# zero_board.net
KiCad netlist of a schematic drawn in EAGLE
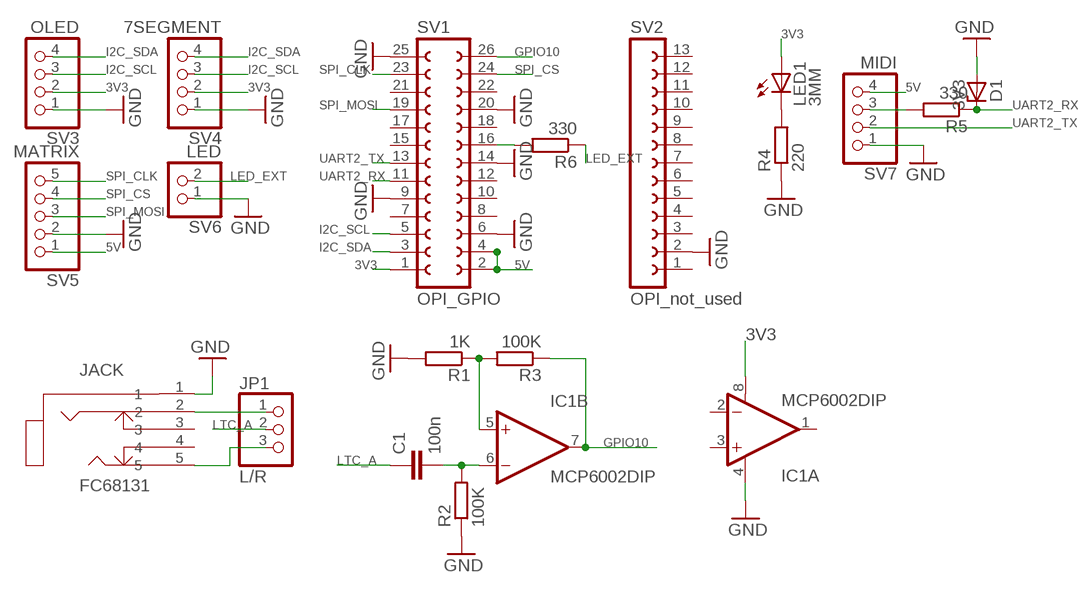
[diagram p0: schematic, sheet 1]

(export (version "E")
  (design (tool "Eeschema 10.0.6"))
  (components
    (comp (ref "C1")
      (value "100n")
      (footprint "eagle-import:C050-024X044")
      (libsource (lib "eagle-import") (part "C-EU050-024X044"))
    )
    (comp (ref "D1")
      (value "3V3")
      (footprint "eagle-import:ZDIO-2.5")
      (libsource (lib "eagle-import") (part "ZENER-DIODEZD-2.5"))
    )
    (comp (ref "IC1")
      (value "MCP6002DIP")
      (footprint "eagle-import:DIP08")
      (libsource (lib "eagle-import") (part "MCP6002DIP"))
    )
    (comp (ref "JACK")
      (value "FC68131")
      (footprint "eagle-import:FC68131-5P")
      (libsource (lib "eagle-import") (part "FC68131"))
    )
    (comp (ref "JP1")
      (value "L/R")
      (footprint "eagle-import:1X03")
      (libsource (lib "eagle-import") (part "PINHD-1X3"))
    )
    (comp (ref "LED1")
      (value "3MM")
      (footprint "eagle-import:LED3MM")
      (libsource (lib "eagle-import") (part "LED3MM"))
    )
    (comp (ref "R1")
      (value "1K")
      (footprint "eagle-import:0204_5")
      (libsource (lib "eagle-import") (part "R-EU_0204/5"))
    )
    (comp (ref "R2")
      (value "100K")
      (footprint "eagle-import:0204_5")
      (libsource (lib "eagle-import") (part "R-EU_0204/5"))
    )
    (comp (ref "R3")
      (value "100K")
      (footprint "eagle-import:0204_5")
      (libsource (lib "eagle-import") (part "R-EU_0204/5"))
    )
    (comp (ref "R4")
      (value "220")
      (footprint "eagle-import:0204_5")
      (libsource (lib "eagle-import") (part "R-EU_0204/5"))
    )
    (comp (ref "R5")
      (value "330")
      (footprint "eagle-import:0204V")
      (libsource (lib "eagle-import") (part "R-EU_0204/2V"))
    )
    (comp (ref "R6")
      (value "330")
      (footprint "eagle-import:0204V")
      (libsource (lib "eagle-import") (part "R-EU_0204/2V"))
    )
    (comp (ref "SV1")
      (value "OPI_GPIO")
      (footprint "eagle-import:FE13-2")
      (libsource (lib "eagle-import") (part "FE13-2"))
    )
    (comp (ref "SV2")
      (value "OPI_not_used")
      (footprint "eagle-import:FE13")
      (libsource (lib "eagle-import") (part "FE13-1"))
    )
    (comp (ref "SV3")
      (value "OLED")
      (footprint "eagle-import:1X04")
      (libsource (lib "eagle-import") (part "PINHD-1X4"))
    )
    (comp (ref "SV4")
      (value "7SEGMENT")
      (footprint "eagle-import:1X04")
      (libsource (lib "eagle-import") (part "PINHD-1X4"))
    )
    (comp (ref "SV5")
      (value "MATRIX")
      (footprint "eagle-import:1X05")
      (libsource (lib "eagle-import") (part "PINHD-1X5"))
    )
    (comp (ref "SV6")
      (value "LED")
      (footprint "eagle-import:1X02")
      (libsource (lib "eagle-import") (part "PINHD-1X2"))
    )
    (comp (ref "SV7")
      (value "MIDI")
      (footprint "eagle-import:1X04")
      (libsource (lib "eagle-import") (part "PINHD-1X4"))
    )
  )
  (nets
    (net (code "1") (name "/3V3") (class "Default")
      (node (ref "IC1") (pin "8") (pinfunction "V+_8") (pintype "power_in"))
      (node (ref "LED1") (pin "A") (pinfunction "A_A") (pintype "passive"))
      (node (ref "SV1") (pin "1") (pinfunction "1_1") (pintype "passive"))
      (node (ref "SV3") (pin "2") (pinfunction "2_2") (pintype "passive"))
      (node (ref "SV4") (pin "2") (pinfunction "2_2") (pintype "passive"))
    )
    (net (code "2") (name "/5V") (class "Default")
      (node (ref "SV1") (pin "2") (pinfunction "2_2") (pintype "passive"))
      (node (ref "SV1") (pin "4") (pinfunction "4_4") (pintype "passive"))
      (node (ref "SV5") (pin "1") (pinfunction "1_1") (pintype "passive"))
      (node (ref "SV7") (pin "4") (pinfunction "4_4") (pintype "passive"))
    )
    (net (code "3") (name "/GPIO10") (class "Default")
      (node (ref "IC1") (pin "7") (pinfunction "OUT_7") (pintype "output"))
      (node (ref "R3") (pin "1") (pinfunction "1_1") (pintype "passive"))
      (node (ref "SV1") (pin "26") (pinfunction "26_26") (pintype "passive"))
    )
    (net (code "4") (name "/I2C_SCL") (class "Default")
      (node (ref "SV1") (pin "5") (pinfunction "5_5") (pintype "passive"))
      (node (ref "SV3") (pin "3") (pinfunction "3_3") (pintype "passive"))
      (node (ref "SV4") (pin "3") (pinfunction "3_3") (pintype "passive"))
    )
    (net (code "5") (name "/I2C_SDA") (class "Default")
      (node (ref "SV1") (pin "3") (pinfunction "3_3") (pintype "passive"))
      (node (ref "SV3") (pin "4") (pinfunction "4_4") (pintype "passive"))
      (node (ref "SV4") (pin "4") (pinfunction "4_4") (pintype "passive"))
    )
    (net (code "6") (name "/LED_EXT") (class "Default")
      (node (ref "R6") (pin "1") (pinfunction "1_1") (pintype "passive"))
      (node (ref "SV6") (pin "2") (pinfunction "2_2") (pintype "passive"))
    )
    (net (code "7") (name "/LTC_A") (class "Default")
      (node (ref "C1") (pin "1") (pinfunction "1_1") (pintype "passive"))
      (node (ref "JP1") (pin "2") (pinfunction "2_2") (pintype "passive"))
    )
    (net (code "8") (name "/SPI_CLK") (class "Default")
      (node (ref "SV1") (pin "23") (pinfunction "23_23") (pintype "passive"))
      (node (ref "SV5") (pin "5") (pinfunction "5_5") (pintype "passive"))
    )
    (net (code "9") (name "/SPI_CS") (class "Default")
      (node (ref "SV1") (pin "24") (pinfunction "24_24") (pintype "passive"))
      (node (ref "SV5") (pin "4") (pinfunction "4_4") (pintype "passive"))
    )
    (net (code "10") (name "/SPI_MOSI") (class "Default")
      (node (ref "SV1") (pin "19") (pinfunction "19_19") (pintype "passive"))
      (node (ref "SV5") (pin "3") (pinfunction "3_3") (pintype "passive"))
    )
    (net (code "11") (name "/UART2_RX") (class "Default")
      (node (ref "D1") (pin "C") (pinfunction "C_C") (pintype "passive"))
      (node (ref "R5") (pin "1") (pinfunction "1_1") (pintype "passive"))
      (node (ref "SV1") (pin "11") (pinfunction "11_11") (pintype "passive"))
    )
    (net (code "12") (name "/UART2_TX") (class "Default")
      (node (ref "SV1") (pin "13") (pinfunction "13_13") (pintype "passive"))
      (node (ref "SV7") (pin "2") (pinfunction "2_2") (pintype "passive"))
    )
    (net (code "13") (name "GND") (class "Default")
      (node (ref "D1") (pin "A") (pinfunction "A_A") (pintype "passive"))
      (node (ref "IC1") (pin "4") (pinfunction "V-_4") (pintype "power_in"))
      (node (ref "JACK") (pin "1") (pinfunction "1_1") (pintype "bidirectional"))
      (node (ref "R1") (pin "2") (pinfunction "2_2") (pintype "passive"))
      (node (ref "R2") (pin "1") (pinfunction "1_1") (pintype "passive"))
      (node (ref "R4") (pin "1") (pinfunction "1_1") (pintype "passive"))
      (node (ref "SV1") (pin "14") (pinfunction "14_14") (pintype "passive"))
      (node (ref "SV1") (pin "20") (pinfunction "20_20") (pintype "passive"))
      (node (ref "SV1") (pin "25") (pinfunction "25_25") (pintype "passive"))
      (node (ref "SV1") (pin "6") (pinfunction "6_6") (pintype "passive"))
      (node (ref "SV1") (pin "9") (pinfunction "9_9") (pintype "passive"))
      (node (ref "SV2") (pin "2") (pinfunction "2_2") (pintype "passive"))
      (node (ref "SV3") (pin "1") (pinfunction "1_1") (pintype "passive"))
      (node (ref "SV4") (pin "1") (pinfunction "1_1") (pintype "passive"))
      (node (ref "SV5") (pin "2") (pinfunction "2_2") (pintype "passive"))
      (node (ref "SV6") (pin "1") (pinfunction "1_1") (pintype "passive"))
      (node (ref "SV7") (pin "1") (pinfunction "1_1") (pintype "passive"))
    )
    (net (code "14") (name "Net-(IC1B-+IN)") (class "Default")
      (node (ref "IC1") (pin "5") (pinfunction "+IN_5") (pintype "input"))
      (node (ref "R1") (pin "1") (pinfunction "1_1") (pintype "passive"))
      (node (ref "R3") (pin "2") (pinfunction "2_2") (pintype "passive"))
    )
    (net (code "15") (name "Net-(IC1B--IN)") (class "Default")
      (node (ref "C1") (pin "2") (pinfunction "2_2") (pintype "passive"))
      (node (ref "IC1") (pin "6") (pinfunction "-IN_6") (pintype "input"))
      (node (ref "R2") (pin "2") (pinfunction "2_2") (pintype "passive"))
    )
    (net (code "16") (name "Net-(JACK-Pad2)") (class "Default")
      (node (ref "JACK") (pin "2") (pinfunction "2_2") (pintype "bidirectional"))
      (node (ref "JP1") (pin "1") (pinfunction "1_1") (pintype "passive"))
    )
    (net (code "17") (name "Net-(JACK-Pad5)") (class "Default")
      (node (ref "JACK") (pin "5") (pinfunction "5_5") (pintype "bidirectional"))
      (node (ref "JP1") (pin "3") (pinfunction "3_3") (pintype "passive"))
    )
    (net (code "18") (name "Net-(LED1-C)") (class "Default")
      (node (ref "LED1") (pin "K") (pinfunction "C_K") (pintype "passive"))
      (node (ref "R4") (pin "2") (pinfunction "2_2") (pintype "passive"))
    )
    (net (code "19") (name "Net-(R5-Pad2)") (class "Default")
      (node (ref "R5") (pin "2") (pinfunction "2_2") (pintype "passive"))
      (node (ref "SV7") (pin "3") (pinfunction "3_3") (pintype "passive"))
    )
    (net (code "20") (name "Net-(R6-Pad2)") (class "Default")
      (node (ref "R6") (pin "2") (pinfunction "2_2") (pintype "passive"))
      (node (ref "SV1") (pin "16") (pinfunction "16_16") (pintype "passive"))
    )
    (net (code "21") (name "unconnected-(IC1A-+IN-Pad3)") (class "Default")
      (node (ref "IC1") (pin "3") (pinfunction "+IN_3") (pintype "input"))
    )
    (net (code "22") (name "unconnected-(IC1A--IN-Pad2)") (class "Default")
      (node (ref "IC1") (pin "2") (pinfunction "-IN_2") (pintype "input"))
    )
    (net (code "23") (name "unconnected-(IC1A-OUT-Pad1)") (class "Default")
      (node (ref "IC1") (pin "1") (pinfunction "OUT_1") (pintype "output"))
    )
    (net (code "24") (name "unconnected-(JACK-Pad3)") (class "Default")
      (node (ref "JACK") (pin "3") (pinfunction "3_3") (pintype "bidirectional"))
    )
    (net (code "25") (name "unconnected-(JACK-Pad4)") (class "Default")
      (node (ref "JACK") (pin "4") (pinfunction "4_4") (pintype "bidirectional"))
    )
    (net (code "26") (name "unconnected-(SV1-Pad7)") (class "Default")
      (node (ref "SV1") (pin "7") (pinfunction "7_7") (pintype "passive"))
    )
    (net (code "27") (name "unconnected-(SV1-Pad8)") (class "Default")
      (node (ref "SV1") (pin "8") (pinfunction "8_8") (pintype "passive"))
    )
    (net (code "28") (name "unconnected-(SV1-Pad10)") (class "Default")
      (node (ref "SV1") (pin "10") (pinfunction "10_10") (pintype "passive"))
    )
    (net (code "29") (name "unconnected-(SV1-Pad12)") (class "Default")
      (node (ref "SV1") (pin "12") (pinfunction "12_12") (pintype "passive"))
    )
    (net (code "30") (name "unconnected-(SV1-Pad15)") (class "Default")
      (node (ref "SV1") (pin "15") (pinfunction "15_15") (pintype "passive"))
    )
    (net (code "31") (name "unconnected-(SV1-Pad17)") (class "Default")
      (node (ref "SV1") (pin "17") (pinfunction "17_17") (pintype "passive"))
    )
    (net (code "32") (name "unconnected-(SV1-Pad18)") (class "Default")
      (node (ref "SV1") (pin "18") (pinfunction "18_18") (pintype "passive"))
    )
    (net (code "33") (name "unconnected-(SV1-Pad21)") (class "Default")
      (node (ref "SV1") (pin "21") (pinfunction "21_21") (pintype "passive"))
    )
    (net (code "34") (name "unconnected-(SV1-Pad22)") (class "Default")
      (node (ref "SV1") (pin "22") (pinfunction "22_22") (pintype "passive"))
    )
    (net (code "35") (name "unconnected-(SV2-Pad1)") (class "Default")
      (node (ref "SV2") (pin "1") (pinfunction "1_1") (pintype "passive"))
    )
    (net (code "36") (name "unconnected-(SV2-Pad3)") (class "Default")
      (node (ref "SV2") (pin "3") (pinfunction "3_3") (pintype "passive"))
    )
    (net (code "37") (name "unconnected-(SV2-Pad4)") (class "Default")
      (node (ref "SV2") (pin "4") (pinfunction "4_4") (pintype "passive"))
    )
    (net (code "38") (name "unconnected-(SV2-Pad5)") (class "Default")
      (node (ref "SV2") (pin "5") (pinfunction "5_5") (pintype "passive"))
    )
    (net (code "39") (name "unconnected-(SV2-Pad6)") (class "Default")
      (node (ref "SV2") (pin "6") (pinfunction "6_6") (pintype "passive"))
    )
    (net (code "40") (name "unconnected-(SV2-Pad7)") (class "Default")
      (node (ref "SV2") (pin "7") (pinfunction "7_7") (pintype "passive"))
    )
    (net (code "41") (name "unconnected-(SV2-Pad8)") (class "Default")
      (node (ref "SV2") (pin "8") (pinfunction "8_8") (pintype "passive"))
    )
    (net (code "42") (name "unconnected-(SV2-Pad9)") (class "Default")
      (node (ref "SV2") (pin "9") (pinfunction "9_9") (pintype "passive"))
    )
    (net (code "43") (name "unconnected-(SV2-Pad10)") (class "Default")
      (node (ref "SV2") (pin "10") (pinfunction "10_10") (pintype "passive"))
    )
    (net (code "44") (name "unconnected-(SV2-Pad11)") (class "Default")
      (node (ref "SV2") (pin "11") (pinfunction "11_11") (pintype "passive"))
    )
    (net (code "45") (name "unconnected-(SV2-Pad12)") (class "Default")
      (node (ref "SV2") (pin "12") (pinfunction "12_12") (pintype "passive"))
    )
    (net (code "46") (name "unconnected-(SV2-Pad13)") (class "Default")
      (node (ref "SV2") (pin "13") (pinfunction "13_13") (pintype "passive"))
    )
  )
)
